# uMouse.net
KiCad netlist of a schematic drawn in EAGLE
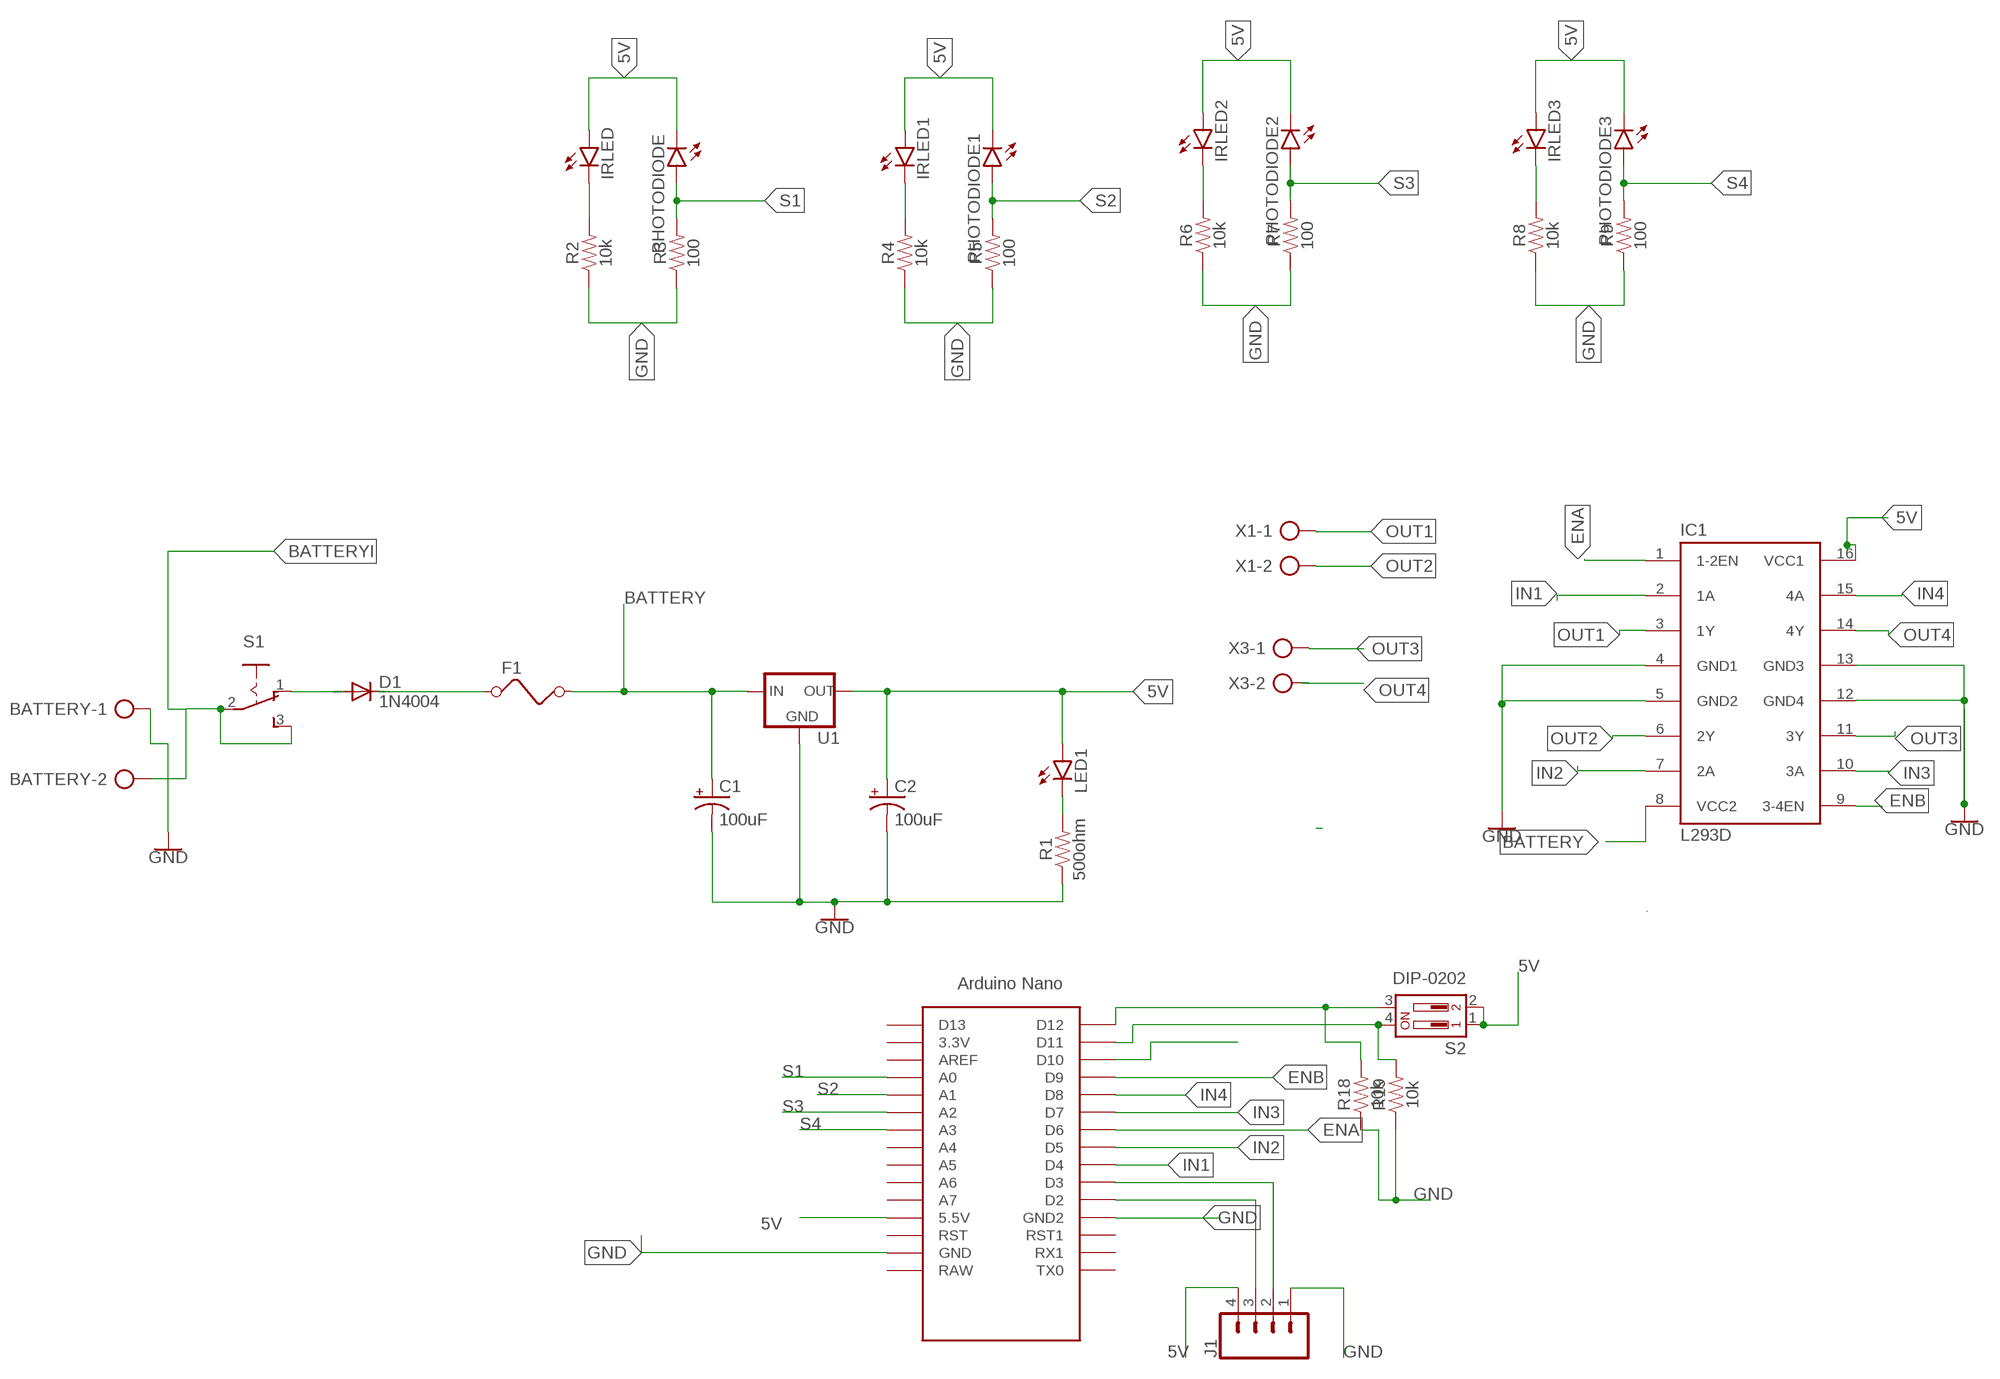
[diagram p0: schematic, sheet 1]

(export (version "E")
  (design (tool "Eeschema 10.0.6"))
  (components
    (comp (ref "BATTERY")
      (value "AK500/2-H")
      (footprint "eagle-import:AK500_2-H")
      (libsource (lib "eagle-import") (part "AK500/2-H"))
    )
    (comp (ref "C1")
      (value "100uF")
      (footprint "eagle-import:CPOL-RADIAL-2.5MM-6.5MM")
      (libsource (lib "eagle-import") (part "100UF-POLAR-RADIAL-2.5MM-25V-20%"))
    )
    (comp (ref "C2")
      (value "100uF")
      (footprint "eagle-import:CPOL-RADIAL-2.5MM-6.5MM")
      (libsource (lib "eagle-import") (part "100UF-POLAR-RADIAL-2.5MM-25V-20%"))
    )
    (comp (ref "D1")
      (value "1N4004")
      (footprint "eagle-import:DO41-10")
      (libsource (lib "eagle-import") (part "1N4004"))
    )
    (comp (ref "F1")
      (value "FUSE")
      (footprint "eagle-import:FUSE")
      (libsource (lib "eagle-import") (part "FUSE"))
    )
    (comp (ref "IC1")
      (value "L293D")
      (footprint "eagle-import:DIL16")
      (libsource (lib "eagle-import") (part "L293D"))
    )
    (comp (ref "IRLED")
      (value "LED5MM")
      (footprint "eagle-import:LED5MM")
      (libsource (lib "eagle-import") (part "LED5MM"))
    )
    (comp (ref "IRLED1")
      (value "LED5MM")
      (footprint "eagle-import:LED5MM")
      (libsource (lib "eagle-import") (part "LED5MM"))
    )
    (comp (ref "IRLED2")
      (value "LED5MM")
      (footprint "eagle-import:LED5MM")
      (libsource (lib "eagle-import") (part "LED5MM"))
    )
    (comp (ref "IRLED3")
      (value "LED5MM")
      (footprint "eagle-import:LED5MM")
      (libsource (lib "eagle-import") (part "LED5MM"))
    )
    (comp (ref "J1")
      (value "CONN_04")
      (footprint "eagle-import:1X04")
      (libsource (lib "eagle-import") (part "CONN_04"))
    )
    (comp (ref "LED1")
      (value "LED3MM")
      (footprint "eagle-import:LED3MM")
      (libsource (lib "eagle-import") (part "LED3MM"))
    )
    (comp (ref "PHOTODIODE")
      (value "LED5MM")
      (footprint "eagle-import:LED5MM")
      (libsource (lib "eagle-import") (part "LED5MM"))
    )
    (comp (ref "PHOTODIODE1")
      (value "LED5MM")
      (footprint "eagle-import:LED5MM")
      (libsource (lib "eagle-import") (part "LED5MM"))
    )
    (comp (ref "PHOTODIODE2")
      (value "LED5MM")
      (footprint "eagle-import:LED5MM")
      (libsource (lib "eagle-import") (part "LED5MM"))
    )
    (comp (ref "PHOTODIODE3")
      (value "LED5MM")
      (footprint "eagle-import:LED5MM")
      (libsource (lib "eagle-import") (part "LED5MM"))
    )
    (comp (ref "R1")
      (value "500ohm")
      (footprint "eagle-import:AXIAL-0.3")
      (libsource (lib "eagle-import") (part "10MOHM-HORIZ-1/4W-5%"))
    )
    (comp (ref "R2")
      (value "10k")
      (footprint "eagle-import:AXIAL-0.3")
      (libsource (lib "eagle-import") (part "10MOHM-HORIZ-1/4W-5%"))
    )
    (comp (ref "R3")
      (value "100")
      (footprint "eagle-import:AXIAL-0.3")
      (libsource (lib "eagle-import") (part "10MOHM-HORIZ-1/4W-5%"))
    )
    (comp (ref "R4")
      (value "10k")
      (footprint "eagle-import:AXIAL-0.3")
      (libsource (lib "eagle-import") (part "10MOHM-HORIZ-1/4W-5%"))
    )
    (comp (ref "R5")
      (value "100")
      (footprint "eagle-import:AXIAL-0.3")
      (libsource (lib "eagle-import") (part "10MOHM-HORIZ-1/4W-5%"))
    )
    (comp (ref "R6")
      (value "10k")
      (footprint "eagle-import:AXIAL-0.3")
      (libsource (lib "eagle-import") (part "10MOHM-HORIZ-1/4W-5%"))
    )
    (comp (ref "R7")
      (value "100")
      (footprint "eagle-import:AXIAL-0.3")
      (libsource (lib "eagle-import") (part "10MOHM-HORIZ-1/4W-5%"))
    )
    (comp (ref "R8")
      (value "10k")
      (footprint "eagle-import:AXIAL-0.3")
      (libsource (lib "eagle-import") (part "10MOHM-HORIZ-1/4W-5%"))
    )
    (comp (ref "R9")
      (value "100")
      (footprint "eagle-import:AXIAL-0.3")
      (libsource (lib "eagle-import") (part "10MOHM-HORIZ-1/4W-5%"))
    )
    (comp (ref "R18")
      (value "10k")
      (footprint "eagle-import:AXIAL-0.3")
      (libsource (lib "eagle-import") (part "10MOHM-HORIZ-1/4W-5%"))
    )
    (comp (ref "R19")
      (value "10k")
      (footprint "eagle-import:AXIAL-0.3")
      (libsource (lib "eagle-import") (part "10MOHM-HORIZ-1/4W-5%"))
    )
    (comp (ref "S1")
      (value "255SB")
      (footprint "eagle-import:255SB")
      (libsource (lib "eagle-import") (part "255SB"))
    )
    (comp (ref "S2")
      (value "DIP-0202")
      (footprint "eagle-import:DIPSWITCH-02")
      (libsource (lib "eagle-import") (part "DIP-0202"))
    )
    (comp (ref "U$2")
      (value "NANO")
      (footprint "eagle-import:NANO")
      (libsource (lib "eagle-import") (part "NANO"))
    )
    (comp (ref "U1")
      (value "78XXS")
      (footprint "eagle-import:78XXS")
      (libsource (lib "eagle-import") (part "78XXS"))
    )
    (comp (ref "X1")
      (value "AK500/2-H")
      (footprint "eagle-import:AK500_2-H")
      (libsource (lib "eagle-import") (part "AK500/2-H"))
    )
    (comp (ref "X3")
      (value "AK500/2-H")
      (footprint "eagle-import:AK500_2-H")
      (libsource (lib "eagle-import") (part "AK500/2-H"))
    )
  )
  (nets
    (net (code "1") (name "5V") (class "Default")
      (node (ref "C2") (pin "1") (pinfunction "+_1") (pintype "passive"))
      (node (ref "IC1") (pin "16") (pinfunction "VCC1_16") (pintype "power_in"))
      (node (ref "IRLED") (pin "A") (pinfunction "A_A") (pintype "passive"))
      (node (ref "IRLED1") (pin "A") (pinfunction "A_A") (pintype "passive"))
      (node (ref "IRLED2") (pin "A") (pinfunction "A_A") (pintype "passive"))
      (node (ref "IRLED3") (pin "A") (pinfunction "A_A") (pintype "passive"))
      (node (ref "J1") (pin "4") (pinfunction "4_4") (pintype "passive"))
      (node (ref "LED1") (pin "A") (pinfunction "A_A") (pintype "passive"))
      (node (ref "PHOTODIODE") (pin "K") (pinfunction "C_K") (pintype "passive"))
      (node (ref "PHOTODIODE1") (pin "K") (pinfunction "C_K") (pintype "passive"))
      (node (ref "PHOTODIODE2") (pin "K") (pinfunction "C_K") (pintype "passive"))
      (node (ref "PHOTODIODE3") (pin "K") (pinfunction "C_K") (pintype "passive"))
      (node (ref "S2") (pin "1") (pinfunction "P$1_1") (pintype "bidirectional"))
      (node (ref "S2") (pin "2") (pinfunction "P$2_2") (pintype "bidirectional"))
      (node (ref "U$2") (pin "5V") (pinfunction "5.5V_5V") (pintype "bidirectional"))
      (node (ref "U1") (pin "OUT") (pinfunction "OUT_OUT") (pintype "passive"))
    )
    (net (code "2") (name "BATTERY") (class "Default")
      (node (ref "C1") (pin "1") (pinfunction "+_1") (pintype "passive"))
      (node (ref "F1") (pin "2") (pinfunction "2_2") (pintype "passive"))
      (node (ref "IC1") (pin "8") (pinfunction "VCC2_8") (pintype "power_in"))
      (node (ref "U1") (pin "IN") (pinfunction "IN_IN") (pintype "input"))
    )
    (net (code "3") (name "BATTERYI") (class "Default")
      (node (ref "BATTERY") (pin "2") (pinfunction "KL_2") (pintype "passive"))
      (node (ref "S1") (pin "2") (pinfunction "P_2") (pintype "passive"))
      (node (ref "S1") (pin "3") (pinfunction "S_3") (pintype "passive"))
    )
    (net (code "4") (name "ENA") (class "Default")
      (node (ref "IC1") (pin "1") (pinfunction "1-2EN_1") (pintype "input"))
      (node (ref "U$2") (pin "D6") (pinfunction "D6_D6") (pintype "bidirectional"))
    )
    (net (code "5") (name "ENB") (class "Default")
      (node (ref "IC1") (pin "9") (pinfunction "3-4EN_9") (pintype "input"))
      (node (ref "U$2") (pin "D9") (pinfunction "D9_D9") (pintype "bidirectional"))
    )
    (net (code "6") (name "GND") (class "Default")
      (node (ref "BATTERY") (pin "1") (pinfunction "KL_1") (pintype "passive"))
      (node (ref "C1") (pin "2") (pinfunction "-_2") (pintype "passive"))
      (node (ref "C2") (pin "2") (pinfunction "-_2") (pintype "passive"))
      (node (ref "IC1") (pin "12") (pinfunction "GND4_12") (pintype "power_in"))
      (node (ref "IC1") (pin "13") (pinfunction "GND3_13") (pintype "power_in"))
      (node (ref "IC1") (pin "4") (pinfunction "GND1_4") (pintype "power_in"))
      (node (ref "IC1") (pin "5") (pinfunction "GND2_5") (pintype "power_in"))
      (node (ref "J1") (pin "1") (pinfunction "1_1") (pintype "passive"))
      (node (ref "R1") (pin "P$1") (pinfunction "1_P$1") (pintype "passive"))
      (node (ref "R18") (pin "P$1") (pinfunction "1_P$1") (pintype "passive"))
      (node (ref "R19") (pin "P$1") (pinfunction "1_P$1") (pintype "passive"))
      (node (ref "R2") (pin "P$1") (pinfunction "1_P$1") (pintype "passive"))
      (node (ref "R3") (pin "P$1") (pinfunction "1_P$1") (pintype "passive"))
      (node (ref "R4") (pin "P$1") (pinfunction "1_P$1") (pintype "passive"))
      (node (ref "R5") (pin "P$1") (pinfunction "1_P$1") (pintype "passive"))
      (node (ref "R6") (pin "P$1") (pinfunction "1_P$1") (pintype "passive"))
      (node (ref "R7") (pin "P$1") (pinfunction "1_P$1") (pintype "passive"))
      (node (ref "R8") (pin "P$1") (pinfunction "1_P$1") (pintype "passive"))
      (node (ref "R9") (pin "P$1") (pinfunction "1_P$1") (pintype "passive"))
      (node (ref "U$2") (pin "GND") (pinfunction "GND_GND") (pintype "bidirectional"))
      (node (ref "U$2") (pin "GND1") (pinfunction "GND2_GND1") (pintype "bidirectional"))
      (node (ref "U1") (pin "GND") (pinfunction "GND_GND") (pintype "input"))
    )
    (net (code "7") (name "IN1") (class "Default")
      (node (ref "IC1") (pin "2") (pinfunction "1A_2") (pintype "input"))
      (node (ref "U$2") (pin "D4") (pinfunction "D4_D4") (pintype "bidirectional"))
    )
    (net (code "8") (name "IN2") (class "Default")
      (node (ref "IC1") (pin "7") (pinfunction "2A_7") (pintype "input"))
      (node (ref "U$2") (pin "D5") (pinfunction "D5_D5") (pintype "bidirectional"))
    )
    (net (code "9") (name "IN3") (class "Default")
      (node (ref "IC1") (pin "10") (pinfunction "3A_10") (pintype "input"))
      (node (ref "U$2") (pin "D7") (pinfunction "D7_D7") (pintype "bidirectional"))
    )
    (net (code "10") (name "IN4") (class "Default")
      (node (ref "IC1") (pin "15") (pinfunction "4A_15") (pintype "input"))
      (node (ref "U$2") (pin "D8") (pinfunction "D8_D8") (pintype "bidirectional"))
    )
    (net (code "11") (name "Net-(D1-PadC)") (class "Default")
      (node (ref "D1") (pin "C") (pinfunction "C_C") (pintype "passive"))
      (node (ref "F1") (pin "1") (pinfunction "1_1") (pintype "passive"))
    )
    (net (code "12") (name "Net-(IRLED-C)") (class "Default")
      (node (ref "IRLED") (pin "K") (pinfunction "C_K") (pintype "passive"))
      (node (ref "R2") (pin "P$2") (pinfunction "2_P$2") (pintype "passive"))
    )
    (net (code "13") (name "Net-(IRLED1-C)") (class "Default")
      (node (ref "IRLED1") (pin "K") (pinfunction "C_K") (pintype "passive"))
      (node (ref "R4") (pin "P$2") (pinfunction "2_P$2") (pintype "passive"))
    )
    (net (code "14") (name "Net-(IRLED2-C)") (class "Default")
      (node (ref "IRLED2") (pin "K") (pinfunction "C_K") (pintype "passive"))
      (node (ref "R6") (pin "P$2") (pinfunction "2_P$2") (pintype "passive"))
    )
    (net (code "15") (name "Net-(IRLED3-C)") (class "Default")
      (node (ref "IRLED3") (pin "K") (pinfunction "C_K") (pintype "passive"))
      (node (ref "R8") (pin "P$2") (pinfunction "2_P$2") (pintype "passive"))
    )
    (net (code "16") (name "Net-(J1-Pad2)") (class "Default")
      (node (ref "J1") (pin "2") (pinfunction "2_2") (pintype "passive"))
      (node (ref "U$2") (pin "D3") (pinfunction "D3_D3") (pintype "bidirectional"))
    )
    (net (code "17") (name "Net-(J1-Pad3)") (class "Default")
      (node (ref "J1") (pin "3") (pinfunction "3_3") (pintype "passive"))
      (node (ref "U$2") (pin "D2") (pinfunction "D2_D2") (pintype "bidirectional"))
    )
    (net (code "18") (name "Net-(LED1-C)") (class "Default")
      (node (ref "LED1") (pin "K") (pinfunction "C_K") (pintype "passive"))
      (node (ref "R1") (pin "P$2") (pinfunction "2_P$2") (pintype "passive"))
    )
    (net (code "19") (name "Net-(R18-2)") (class "Default")
      (node (ref "R18") (pin "P$2") (pinfunction "2_P$2") (pintype "passive"))
      (node (ref "S2") (pin "3") (pinfunction "P$3_3") (pintype "bidirectional"))
      (node (ref "U$2") (pin "D12") (pinfunction "D12_D12") (pintype "bidirectional"))
    )
    (net (code "20") (name "Net-(R19-2)") (class "Default")
      (node (ref "R19") (pin "P$2") (pinfunction "2_P$2") (pintype "passive"))
      (node (ref "S2") (pin "4") (pinfunction "P$4_4") (pintype "bidirectional"))
      (node (ref "U$2") (pin "D11") (pinfunction "D11_D11") (pintype "bidirectional"))
    )
    (net (code "21") (name "Net-(S1-O)") (class "Default")
      (node (ref "D1") (pin "A") (pinfunction "A_A") (pintype "passive"))
      (node (ref "S1") (pin "1") (pinfunction "O_1") (pintype "passive"))
    )
    (net (code "22") (name "OUT1") (class "Default")
      (node (ref "IC1") (pin "3") (pinfunction "1Y_3") (pintype "output"))
      (node (ref "X1") (pin "1") (pinfunction "KL_1") (pintype "passive"))
    )
    (net (code "23") (name "OUT2") (class "Default")
      (node (ref "IC1") (pin "6") (pinfunction "2Y_6") (pintype "output"))
      (node (ref "X1") (pin "2") (pinfunction "KL_2") (pintype "passive"))
    )
    (net (code "24") (name "OUT3") (class "Default")
      (node (ref "IC1") (pin "11") (pinfunction "3Y_11") (pintype "output"))
      (node (ref "X3") (pin "1") (pinfunction "KL_1") (pintype "passive"))
    )
    (net (code "25") (name "OUT4") (class "Default")
      (node (ref "IC1") (pin "14") (pinfunction "4Y_14") (pintype "output"))
      (node (ref "X3") (pin "2") (pinfunction "KL_2") (pintype "passive"))
    )
    (net (code "26") (name "S1") (class "Default")
      (node (ref "PHOTODIODE") (pin "A") (pinfunction "A_A") (pintype "passive"))
      (node (ref "R3") (pin "P$2") (pinfunction "2_P$2") (pintype "passive"))
      (node (ref "U$2") (pin "A0") (pinfunction "A0_A0") (pintype "bidirectional"))
    )
    (net (code "27") (name "S2") (class "Default")
      (node (ref "PHOTODIODE1") (pin "A") (pinfunction "A_A") (pintype "passive"))
      (node (ref "R5") (pin "P$2") (pinfunction "2_P$2") (pintype "passive"))
      (node (ref "U$2") (pin "A1") (pinfunction "A1_A1") (pintype "bidirectional"))
    )
    (net (code "28") (name "S3") (class "Default")
      (node (ref "PHOTODIODE2") (pin "A") (pinfunction "A_A") (pintype "passive"))
      (node (ref "R7") (pin "P$2") (pinfunction "2_P$2") (pintype "passive"))
      (node (ref "U$2") (pin "A2") (pinfunction "A2_A2") (pintype "bidirectional"))
    )
    (net (code "29") (name "S4") (class "Default")
      (node (ref "PHOTODIODE3") (pin "A") (pinfunction "A_A") (pintype "passive"))
      (node (ref "R9") (pin "P$2") (pinfunction "2_P$2") (pintype "passive"))
      (node (ref "U$2") (pin "A3") (pinfunction "A3_A3") (pintype "bidirectional"))
    )
    (net (code "30") (name "unconnected-(U$2-Pad3.3V)") (class "Default")
      (node (ref "U$2") (pin "3.3V") (pinfunction "3.3V_3.3V") (pintype "bidirectional"))
    )
    (net (code "31") (name "unconnected-(U$2-PadA4)") (class "Default")
      (node (ref "U$2") (pin "A4") (pinfunction "A4_A4") (pintype "bidirectional"))
    )
    (net (code "32") (name "unconnected-(U$2-PadA5)") (class "Default")
      (node (ref "U$2") (pin "A5") (pinfunction "A5_A5") (pintype "bidirectional"))
    )
    (net (code "33") (name "unconnected-(U$2-PadA6)") (class "Default")
      (node (ref "U$2") (pin "A6") (pinfunction "A6_A6") (pintype "bidirectional"))
    )
    (net (code "34") (name "unconnected-(U$2-PadA7)") (class "Default")
      (node (ref "U$2") (pin "A7") (pinfunction "A7_A7") (pintype "bidirectional"))
    )
    (net (code "35") (name "unconnected-(U$2-PadAREF)") (class "Default")
      (node (ref "U$2") (pin "AREF") (pinfunction "AREF_AREF") (pintype "bidirectional"))
    )
    (net (code "36") (name "unconnected-(U$2-PadD10)") (class "Default")
      (node (ref "U$2") (pin "D10") (pinfunction "D10_D10") (pintype "bidirectional"))
    )
    (net (code "37") (name "unconnected-(U$2-PadD13)") (class "Default")
      (node (ref "U$2") (pin "D13") (pinfunction "D13_D13") (pintype "bidirectional"))
    )
    (net (code "38") (name "unconnected-(U$2-PadICSP1)") (class "Default")
      (node (ref "U$2") (pin "ICSP1") (pinfunction "ICSP1_ICSP1") (pintype "bidirectional"))
    )
    (net (code "39") (name "unconnected-(U$2-PadICSP2)") (class "Default")
      (node (ref "U$2") (pin "ICSP2") (pinfunction "ICSP2_ICSP2") (pintype "bidirectional"))
    )
    (net (code "40") (name "unconnected-(U$2-PadICSP3)") (class "Default")
      (node (ref "U$2") (pin "ICSP3") (pinfunction "ICSP3_ICSP3") (pintype "bidirectional"))
    )
    (net (code "41") (name "unconnected-(U$2-PadICSP4)") (class "Default")
      (node (ref "U$2") (pin "ICSP4") (pinfunction "ICSP4_ICSP4") (pintype "bidirectional"))
    )
    (net (code "42") (name "unconnected-(U$2-PadICSP5)") (class "Default")
      (node (ref "U$2") (pin "ICSP5") (pinfunction "ICSP5_ICSP5") (pintype "bidirectional"))
    )
    (net (code "43") (name "unconnected-(U$2-PadICSP6)") (class "Default")
      (node (ref "U$2") (pin "ICSP6") (pinfunction "ICSP6_ICSP6") (pintype "bidirectional"))
    )
    (net (code "44") (name "unconnected-(U$2-PadRAW)") (class "Default")
      (node (ref "U$2") (pin "RAW") (pinfunction "RAW_RAW") (pintype "bidirectional"))
    )
    (net (code "45") (name "unconnected-(U$2-PadRST)") (class "Default")
      (node (ref "U$2") (pin "RST") (pinfunction "RST_RST") (pintype "bidirectional"))
    )
    (net (code "46") (name "unconnected-(U$2-PadRST1)") (class "Default")
      (node (ref "U$2") (pin "RST1") (pinfunction "RST1_RST1") (pintype "bidirectional"))
    )
    (net (code "47") (name "unconnected-(U$2-PadRX1)") (class "Default")
      (node (ref "U$2") (pin "RX1") (pinfunction "RX1_RX1") (pintype "bidirectional"))
    )
    (net (code "48") (name "unconnected-(U$2-PadTX0)") (class "Default")
      (node (ref "U$2") (pin "TX0") (pinfunction "TX0_TX0") (pintype "bidirectional"))
    )
  )
)
